# power_2.net
KiCad netlist of a schematic drawn in EAGLE
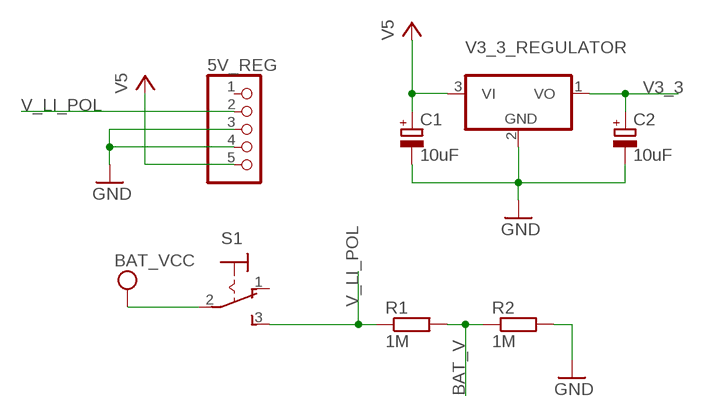
[diagram p0: schematic, sheet 1]

(export (version "E")
  (design (tool "Eeschema 10.0.6"))
  (components
    (comp (ref "5V_REG")
      (value "PINHD-1X5")
      (footprint "eagle-import:1X05")
      (libsource (lib "eagle-import") (part "PINHD-1X5"))
    )
    (comp (ref "C1")
      (value "10uF")
      (footprint "eagle-import:E5-5")
      (libsource (lib "eagle-import") (part "CPOL-EUE5-5"))
    )
    (comp (ref "C2")
      (value "10uF")
      (footprint "eagle-import:E5-5")
      (libsource (lib "eagle-import") (part "CPOL-EUE5-5"))
    )
    (comp (ref "R1")
      (value "1M")
      (footprint "eagle-import:0309_10")
      (libsource (lib "eagle-import") (part "R-EU_0309/10"))
    )
    (comp (ref "R2")
      (value "1M")
      (footprint "eagle-import:0309_10")
      (libsource (lib "eagle-import") (part "R-EU_0309/10"))
    )
    (comp (ref "S1")
      (value "320-916")
      (footprint "eagle-import:320-916")
      (libsource (lib "eagle-import") (part "320-916"))
    )
    (comp (ref "V3_3_REGULATOR")
      (value "7815L")
      (footprint "eagle-import:TO92")
      (libsource (lib "eagle-import") (part "78L15"))
    )
  )
  (nets
    (net (code "1") (name "/BAT_V") (class "Default")
      (node (ref "R1") (pin "2") (pinfunction "2_2") (pintype "passive"))
      (node (ref "R2") (pin "1") (pinfunction "1_1") (pintype "passive"))
    )
    (net (code "2") (name "/V3_3") (class "Default")
      (node (ref "C2") (pin "+") (pinfunction "+_+") (pintype "passive"))
      (node (ref "V3_3_REGULATOR") (pin "1") (pinfunction "VO_1") (pintype "passive"))
    )
    (net (code "3") (name "/V_LI_POL") (class "Default")
      (node (ref "5V_REG") (pin "2") (pinfunction "2_2") (pintype "passive"))
      (node (ref "R1") (pin "1") (pinfunction "1_1") (pintype "passive"))
      (node (ref "S1") (pin "3") (pinfunction "S_3") (pintype "passive"))
    )
    (net (code "4") (name "BAT_VCC") (class "Default")
      (node (ref "5V_REG") (pin "5") (pinfunction "5_5") (pintype "passive"))
      (node (ref "C1") (pin "+") (pinfunction "+_+") (pintype "passive"))
      (node (ref "S1") (pin "2") (pinfunction "P_2") (pintype "passive"))
      (node (ref "V3_3_REGULATOR") (pin "3") (pinfunction "VI_3") (pintype "input"))
    )
    (net (code "5") (name "GND") (class "Default")
      (node (ref "5V_REG") (pin "3") (pinfunction "3_3") (pintype "passive"))
      (node (ref "5V_REG") (pin "4") (pinfunction "4_4") (pintype "passive"))
      (node (ref "C1") (pin "-") (pinfunction "-_-") (pintype "passive"))
      (node (ref "C2") (pin "-") (pinfunction "-_-") (pintype "passive"))
      (node (ref "R2") (pin "2") (pinfunction "2_2") (pintype "passive"))
      (node (ref "V3_3_REGULATOR") (pin "2") (pinfunction "GND_2") (pintype "passive"))
    )
    (net (code "6") (name "unconnected-(5V_REG-Pad1)") (class "Default")
      (node (ref "5V_REG") (pin "1") (pinfunction "1_1") (pintype "passive"))
    )
    (net (code "7") (name "unconnected-(S1-O-Pad1)") (class "Default")
      (node (ref "S1") (pin "1") (pinfunction "O_1") (pintype "passive"))
    )
  )
)
